# IMU.net
KiCad netlist of a schematic drawn in EAGLE
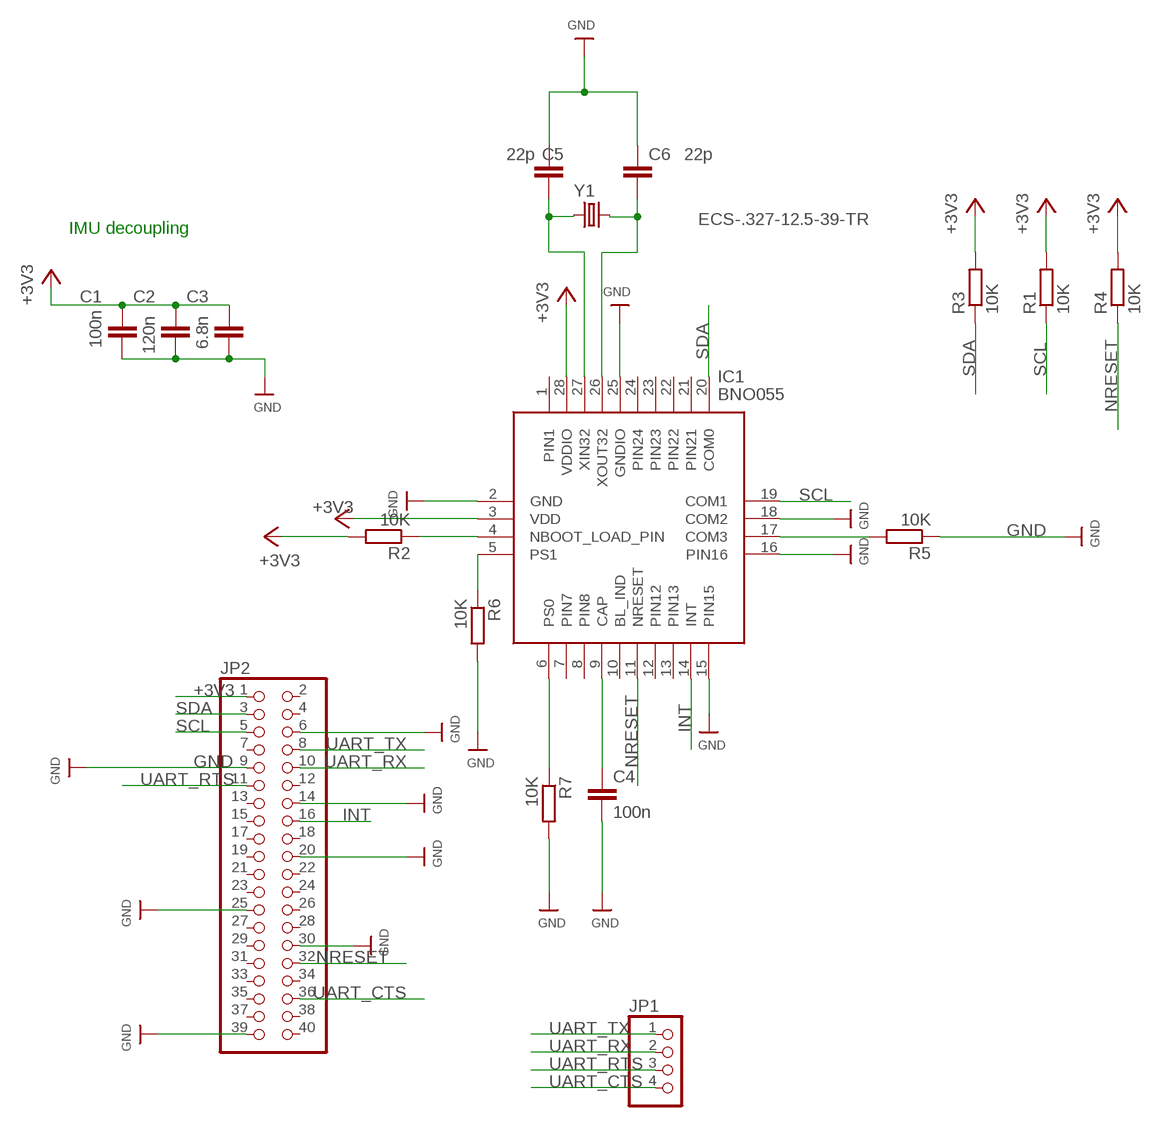
[diagram p0: schematic, sheet 1]

(export (version "E")
  (design (tool "Eeschema 10.0.6"))
  (components
    (comp (ref "C1")
      (value "100n")
      (footprint "eagle-import:C0805")
      (libsource (lib "eagle-import") (part "C-EUC0805"))
    )
    (comp (ref "C2")
      (value "120n")
      (footprint "eagle-import:C0805")
      (libsource (lib "eagle-import") (part "C-EUC0805"))
    )
    (comp (ref "C3")
      (value "6.8n")
      (footprint "eagle-import:C0805")
      (libsource (lib "eagle-import") (part "C-EUC0805"))
    )
    (comp (ref "C4")
      (value "100n")
      (footprint "eagle-import:C0805")
      (libsource (lib "eagle-import") (part "C-EUC0805"))
    )
    (comp (ref "C5")
      (value "22p")
      (footprint "eagle-import:C0805")
      (libsource (lib "eagle-import") (part "C-EUC0805"))
    )
    (comp (ref "C6")
      (value "22p")
      (footprint "eagle-import:C0805")
      (libsource (lib "eagle-import") (part "C-EUC0805"))
    )
    (comp (ref "IC1")
      (value "BNO055")
      (footprint "eagle-import:BNO055")
      (fields (field (name "MOUSER_PART_NUMBER") "262-BNO055"))
      (libsource (lib "eagle-import") (part "BNO055"))
    )
    (comp (ref "JP1")
      (value "PINHD-1X4")
      (footprint "eagle-import:1X04")
      (libsource (lib "eagle-import") (part "PINHD-1X4"))
    )
    (comp (ref "JP2")
      (value "PINHD-2X20")
      (footprint "eagle-import:2X20")
      (libsource (lib "eagle-import") (part "PINHD-2X20"))
    )
    (comp (ref "R1")
      (value "10K")
      (footprint "eagle-import:R0805")
      (libsource (lib "eagle-import") (part "R-EU_R0805"))
    )
    (comp (ref "R2")
      (value "10K")
      (footprint "eagle-import:R0805")
      (libsource (lib "eagle-import") (part "R-EU_R0805"))
    )
    (comp (ref "R3")
      (value "10K")
      (footprint "eagle-import:R0805")
      (libsource (lib "eagle-import") (part "R-EU_R0805"))
    )
    (comp (ref "R4")
      (value "10K")
      (footprint "eagle-import:R0805")
      (libsource (lib "eagle-import") (part "R-EU_R0805"))
    )
    (comp (ref "R5")
      (value "10K")
      (footprint "eagle-import:R0805")
      (libsource (lib "eagle-import") (part "R-EU_R0805"))
    )
    (comp (ref "R6")
      (value "10K")
      (footprint "eagle-import:R0805")
      (libsource (lib "eagle-import") (part "R-EU_R0805"))
    )
    (comp (ref "R7")
      (value "10K")
      (footprint "eagle-import:R0805")
      (libsource (lib "eagle-import") (part "R-EU_R0805"))
    )
    (comp (ref "Y1")
      (value "ECS-.327-12.5-39-TR")
      (footprint "eagle-import:ECS-.327-12.5-39-TR")
      (fields
        (field (name "DIGIKEY_PART_NUMBER") "XC1658TR-ND")
        (field (name "MANUFACTURER") "ECS Inc.")
        (field (name "CREATED_BY") "PCBLayout.com")
      )
      (libsource (lib "eagle-import") (part "ECS-.327-12.5-39-TR"))
    )
  )
  (nets
    (net (code "1") (name "+3V3") (class "Default")
      (node (ref "C1") (pin "1") (pinfunction "1_1") (pintype "passive"))
      (node (ref "C2") (pin "1") (pinfunction "1_1") (pintype "passive"))
      (node (ref "C3") (pin "1") (pinfunction "1_1") (pintype "passive"))
      (node (ref "IC1") (pin "28") (pinfunction "VDDIO_28") (pintype "input"))
      (node (ref "IC1") (pin "3") (pinfunction "VDD_3") (pintype "power_in"))
      (node (ref "JP2") (pin "1") (pinfunction "1_1") (pintype "passive"))
      (node (ref "R1") (pin "2") (pinfunction "2_2") (pintype "passive"))
      (node (ref "R2") (pin "2") (pinfunction "2_2") (pintype "passive"))
      (node (ref "R3") (pin "2") (pinfunction "2_2") (pintype "passive"))
      (node (ref "R4") (pin "2") (pinfunction "2_2") (pintype "passive"))
    )
    (net (code "2") (name "/INT") (class "Default")
      (node (ref "IC1") (pin "14") (pinfunction "INT_14") (pintype "bidirectional"))
      (node (ref "JP2") (pin "16") (pinfunction "16_16") (pintype "passive"))
    )
    (net (code "3") (name "/NRESET") (class "Default")
      (node (ref "IC1") (pin "11") (pinfunction "NRESET_11") (pintype "input"))
      (node (ref "JP2") (pin "32") (pinfunction "32_32") (pintype "passive"))
      (node (ref "R4") (pin "1") (pinfunction "1_1") (pintype "passive"))
    )
    (net (code "4") (name "/SCL") (class "Default")
      (node (ref "IC1") (pin "19") (pinfunction "COM1_19") (pintype "input"))
      (node (ref "JP2") (pin "5") (pinfunction "5_5") (pintype "passive"))
      (node (ref "R1") (pin "1") (pinfunction "1_1") (pintype "passive"))
    )
    (net (code "5") (name "/SDA") (class "Default")
      (node (ref "IC1") (pin "20") (pinfunction "COM0_20") (pintype "bidirectional"))
      (node (ref "JP2") (pin "3") (pinfunction "3_3") (pintype "passive"))
      (node (ref "R3") (pin "1") (pinfunction "1_1") (pintype "passive"))
    )
    (net (code "6") (name "/UART_CTS") (class "Default")
      (node (ref "JP1") (pin "4") (pinfunction "4_4") (pintype "passive"))
      (node (ref "JP2") (pin "36") (pinfunction "36_36") (pintype "passive"))
    )
    (net (code "7") (name "/UART_RTS") (class "Default")
      (node (ref "JP1") (pin "3") (pinfunction "3_3") (pintype "passive"))
      (node (ref "JP2") (pin "11") (pinfunction "11_11") (pintype "passive"))
    )
    (net (code "8") (name "/UART_RX") (class "Default")
      (node (ref "JP1") (pin "2") (pinfunction "2_2") (pintype "passive"))
      (node (ref "JP2") (pin "10") (pinfunction "10_10") (pintype "passive"))
    )
    (net (code "9") (name "/UART_TX") (class "Default")
      (node (ref "JP1") (pin "1") (pinfunction "1_1") (pintype "passive"))
      (node (ref "JP2") (pin "8") (pinfunction "8_8") (pintype "passive"))
    )
    (net (code "10") (name "GND") (class "Default")
      (node (ref "C1") (pin "2") (pinfunction "2_2") (pintype "passive"))
      (node (ref "C2") (pin "2") (pinfunction "2_2") (pintype "passive"))
      (node (ref "C3") (pin "2") (pinfunction "2_2") (pintype "passive"))
      (node (ref "C4") (pin "2") (pinfunction "2_2") (pintype "passive"))
      (node (ref "C5") (pin "1") (pinfunction "1_1") (pintype "passive"))
      (node (ref "C6") (pin "1") (pinfunction "1_1") (pintype "passive"))
      (node (ref "IC1") (pin "15") (pinfunction "PIN15_15") (pintype "bidirectional"))
      (node (ref "IC1") (pin "16") (pinfunction "PIN16_16") (pintype "bidirectional"))
      (node (ref "IC1") (pin "18") (pinfunction "COM2_18") (pintype "input"))
      (node (ref "IC1") (pin "2") (pinfunction "GND_2") (pintype "input"))
      (node (ref "IC1") (pin "25") (pinfunction "GNDIO_25") (pintype "bidirectional"))
      (node (ref "JP2") (pin "14") (pinfunction "14_14") (pintype "passive"))
      (node (ref "JP2") (pin "20") (pinfunction "20_20") (pintype "passive"))
      (node (ref "JP2") (pin "25") (pinfunction "25_25") (pintype "passive"))
      (node (ref "JP2") (pin "30") (pinfunction "30_30") (pintype "passive"))
      (node (ref "JP2") (pin "39") (pinfunction "39_39") (pintype "passive"))
      (node (ref "JP2") (pin "6") (pinfunction "6_6") (pintype "passive"))
      (node (ref "JP2") (pin "9") (pinfunction "9_9") (pintype "passive"))
      (node (ref "R5") (pin "1") (pinfunction "1_1") (pintype "passive"))
      (node (ref "R6") (pin "2") (pinfunction "2_2") (pintype "passive"))
      (node (ref "R7") (pin "2") (pinfunction "2_2") (pintype "passive"))
    )
    (net (code "11") (name "Net-(IC1-CAP)") (class "Default")
      (node (ref "C4") (pin "1") (pinfunction "1_1") (pintype "passive"))
      (node (ref "IC1") (pin "9") (pinfunction "CAP_9") (pintype "power_in"))
    )
    (net (code "12") (name "Net-(IC1-COM3)") (class "Default")
      (node (ref "IC1") (pin "17") (pinfunction "COM3_17") (pintype "bidirectional"))
      (node (ref "R5") (pin "2") (pinfunction "2_2") (pintype "passive"))
    )
    (net (code "13") (name "Net-(IC1-NBOOT_LOAD_PIN)") (class "Default")
      (node (ref "IC1") (pin "4") (pinfunction "NBOOT_LOAD_PIN_4") (pintype "power_in"))
      (node (ref "R2") (pin "1") (pinfunction "1_1") (pintype "passive"))
    )
    (net (code "14") (name "Net-(IC1-PS0)") (class "Default")
      (node (ref "IC1") (pin "6") (pinfunction "PS0_6") (pintype "power_in"))
      (node (ref "R7") (pin "1") (pinfunction "1_1") (pintype "passive"))
    )
    (net (code "15") (name "Net-(IC1-PS1)") (class "Default")
      (node (ref "IC1") (pin "5") (pinfunction "PS1_5") (pintype "input"))
      (node (ref "R6") (pin "1") (pinfunction "1_1") (pintype "passive"))
    )
    (net (code "16") (name "Net-(IC1-XIN32)") (class "Default")
      (node (ref "C5") (pin "2") (pinfunction "2_2") (pintype "passive"))
      (node (ref "IC1") (pin "27") (pinfunction "XIN32_27") (pintype "bidirectional"))
      (node (ref "Y1") (pin "1") (pinfunction "1_1") (pintype "passive"))
    )
    (net (code "17") (name "Net-(IC1-XOUT32)") (class "Default")
      (node (ref "C6") (pin "2") (pinfunction "2_2") (pintype "passive"))
      (node (ref "IC1") (pin "26") (pinfunction "XOUT32_26") (pintype "input"))
      (node (ref "Y1") (pin "2") (pinfunction "2_2") (pintype "passive"))
    )
    (net (code "18") (name "unconnected-(IC1-BL_IND-Pad10)") (class "Default")
      (node (ref "IC1") (pin "10") (pinfunction "BL_IND_10") (pintype "input"))
    )
    (net (code "19") (name "unconnected-(IC1-PIN1-Pad1)") (class "Default")
      (node (ref "IC1") (pin "1") (pinfunction "PIN1_1") (pintype "input"))
    )
    (net (code "20") (name "unconnected-(IC1-PIN7-Pad7)") (class "Default")
      (node (ref "IC1") (pin "7") (pinfunction "PIN7_7") (pintype "input"))
    )
    (net (code "21") (name "unconnected-(IC1-PIN8-Pad8)") (class "Default")
      (node (ref "IC1") (pin "8") (pinfunction "PIN8_8") (pintype "output"))
    )
    (net (code "22") (name "unconnected-(IC1-PIN12-Pad12)") (class "Default")
      (node (ref "IC1") (pin "12") (pinfunction "PIN12_12") (pintype "input"))
    )
    (net (code "23") (name "unconnected-(IC1-PIN13-Pad13)") (class "Default")
      (node (ref "IC1") (pin "13") (pinfunction "PIN13_13") (pintype "input"))
    )
    (net (code "24") (name "unconnected-(IC1-PIN21-Pad21)") (class "Default")
      (node (ref "IC1") (pin "21") (pinfunction "PIN21_21") (pintype "bidirectional"))
    )
    (net (code "25") (name "unconnected-(IC1-PIN22-Pad22)") (class "Default")
      (node (ref "IC1") (pin "22") (pinfunction "PIN22_22") (pintype "input"))
    )
    (net (code "26") (name "unconnected-(IC1-PIN23-Pad23)") (class "Default")
      (node (ref "IC1") (pin "23") (pinfunction "PIN23_23") (pintype "input"))
    )
    (net (code "27") (name "unconnected-(IC1-PIN24-Pad24)") (class "Default")
      (node (ref "IC1") (pin "24") (pinfunction "PIN24_24") (pintype "input"))
    )
    (net (code "28") (name "unconnected-(JP2-Pad2)") (class "Default")
      (node (ref "JP2") (pin "2") (pinfunction "2_2") (pintype "passive"))
    )
    (net (code "29") (name "unconnected-(JP2-Pad4)") (class "Default")
      (node (ref "JP2") (pin "4") (pinfunction "4_4") (pintype "passive"))
    )
    (net (code "30") (name "unconnected-(JP2-Pad7)") (class "Default")
      (node (ref "JP2") (pin "7") (pinfunction "7_7") (pintype "passive"))
    )
    (net (code "31") (name "unconnected-(JP2-Pad12)") (class "Default")
      (node (ref "JP2") (pin "12") (pinfunction "12_12") (pintype "passive"))
    )
    (net (code "32") (name "unconnected-(JP2-Pad13)") (class "Default")
      (node (ref "JP2") (pin "13") (pinfunction "13_13") (pintype "passive"))
    )
    (net (code "33") (name "unconnected-(JP2-Pad15)") (class "Default")
      (node (ref "JP2") (pin "15") (pinfunction "15_15") (pintype "passive"))
    )
    (net (code "34") (name "unconnected-(JP2-Pad17)") (class "Default")
      (node (ref "JP2") (pin "17") (pinfunction "17_17") (pintype "passive"))
    )
    (net (code "35") (name "unconnected-(JP2-Pad18)") (class "Default")
      (node (ref "JP2") (pin "18") (pinfunction "18_18") (pintype "passive"))
    )
    (net (code "36") (name "unconnected-(JP2-Pad19)") (class "Default")
      (node (ref "JP2") (pin "19") (pinfunction "19_19") (pintype "passive"))
    )
    (net (code "37") (name "unconnected-(JP2-Pad21)") (class "Default")
      (node (ref "JP2") (pin "21") (pinfunction "21_21") (pintype "passive"))
    )
    (net (code "38") (name "unconnected-(JP2-Pad22)") (class "Default")
      (node (ref "JP2") (pin "22") (pinfunction "22_22") (pintype "passive"))
    )
    (net (code "39") (name "unconnected-(JP2-Pad23)") (class "Default")
      (node (ref "JP2") (pin "23") (pinfunction "23_23") (pintype "passive"))
    )
    (net (code "40") (name "unconnected-(JP2-Pad24)") (class "Default")
      (node (ref "JP2") (pin "24") (pinfunction "24_24") (pintype "passive"))
    )
    (net (code "41") (name "unconnected-(JP2-Pad26)") (class "Default")
      (node (ref "JP2") (pin "26") (pinfunction "26_26") (pintype "passive"))
    )
    (net (code "42") (name "unconnected-(JP2-Pad27)") (class "Default")
      (node (ref "JP2") (pin "27") (pinfunction "27_27") (pintype "passive"))
    )
    (net (code "43") (name "unconnected-(JP2-Pad28)") (class "Default")
      (node (ref "JP2") (pin "28") (pinfunction "28_28") (pintype "passive"))
    )
    (net (code "44") (name "unconnected-(JP2-Pad29)") (class "Default")
      (node (ref "JP2") (pin "29") (pinfunction "29_29") (pintype "passive"))
    )
    (net (code "45") (name "unconnected-(JP2-Pad31)") (class "Default")
      (node (ref "JP2") (pin "31") (pinfunction "31_31") (pintype "passive"))
    )
    (net (code "46") (name "unconnected-(JP2-Pad33)") (class "Default")
      (node (ref "JP2") (pin "33") (pinfunction "33_33") (pintype "passive"))
    )
    (net (code "47") (name "unconnected-(JP2-Pad34)") (class "Default")
      (node (ref "JP2") (pin "34") (pinfunction "34_34") (pintype "passive"))
    )
    (net (code "48") (name "unconnected-(JP2-Pad35)") (class "Default")
      (node (ref "JP2") (pin "35") (pinfunction "35_35") (pintype "passive"))
    )
    (net (code "49") (name "unconnected-(JP2-Pad37)") (class "Default")
      (node (ref "JP2") (pin "37") (pinfunction "37_37") (pintype "passive"))
    )
    (net (code "50") (name "unconnected-(JP2-Pad38)") (class "Default")
      (node (ref "JP2") (pin "38") (pinfunction "38_38") (pintype "passive"))
    )
    (net (code "51") (name "unconnected-(JP2-Pad40)") (class "Default")
      (node (ref "JP2") (pin "40") (pinfunction "40_40") (pintype "passive"))
    )
  )
)
